# MassHackersBadge2015.net
KiCad netlist of a schematic drawn in EAGLE
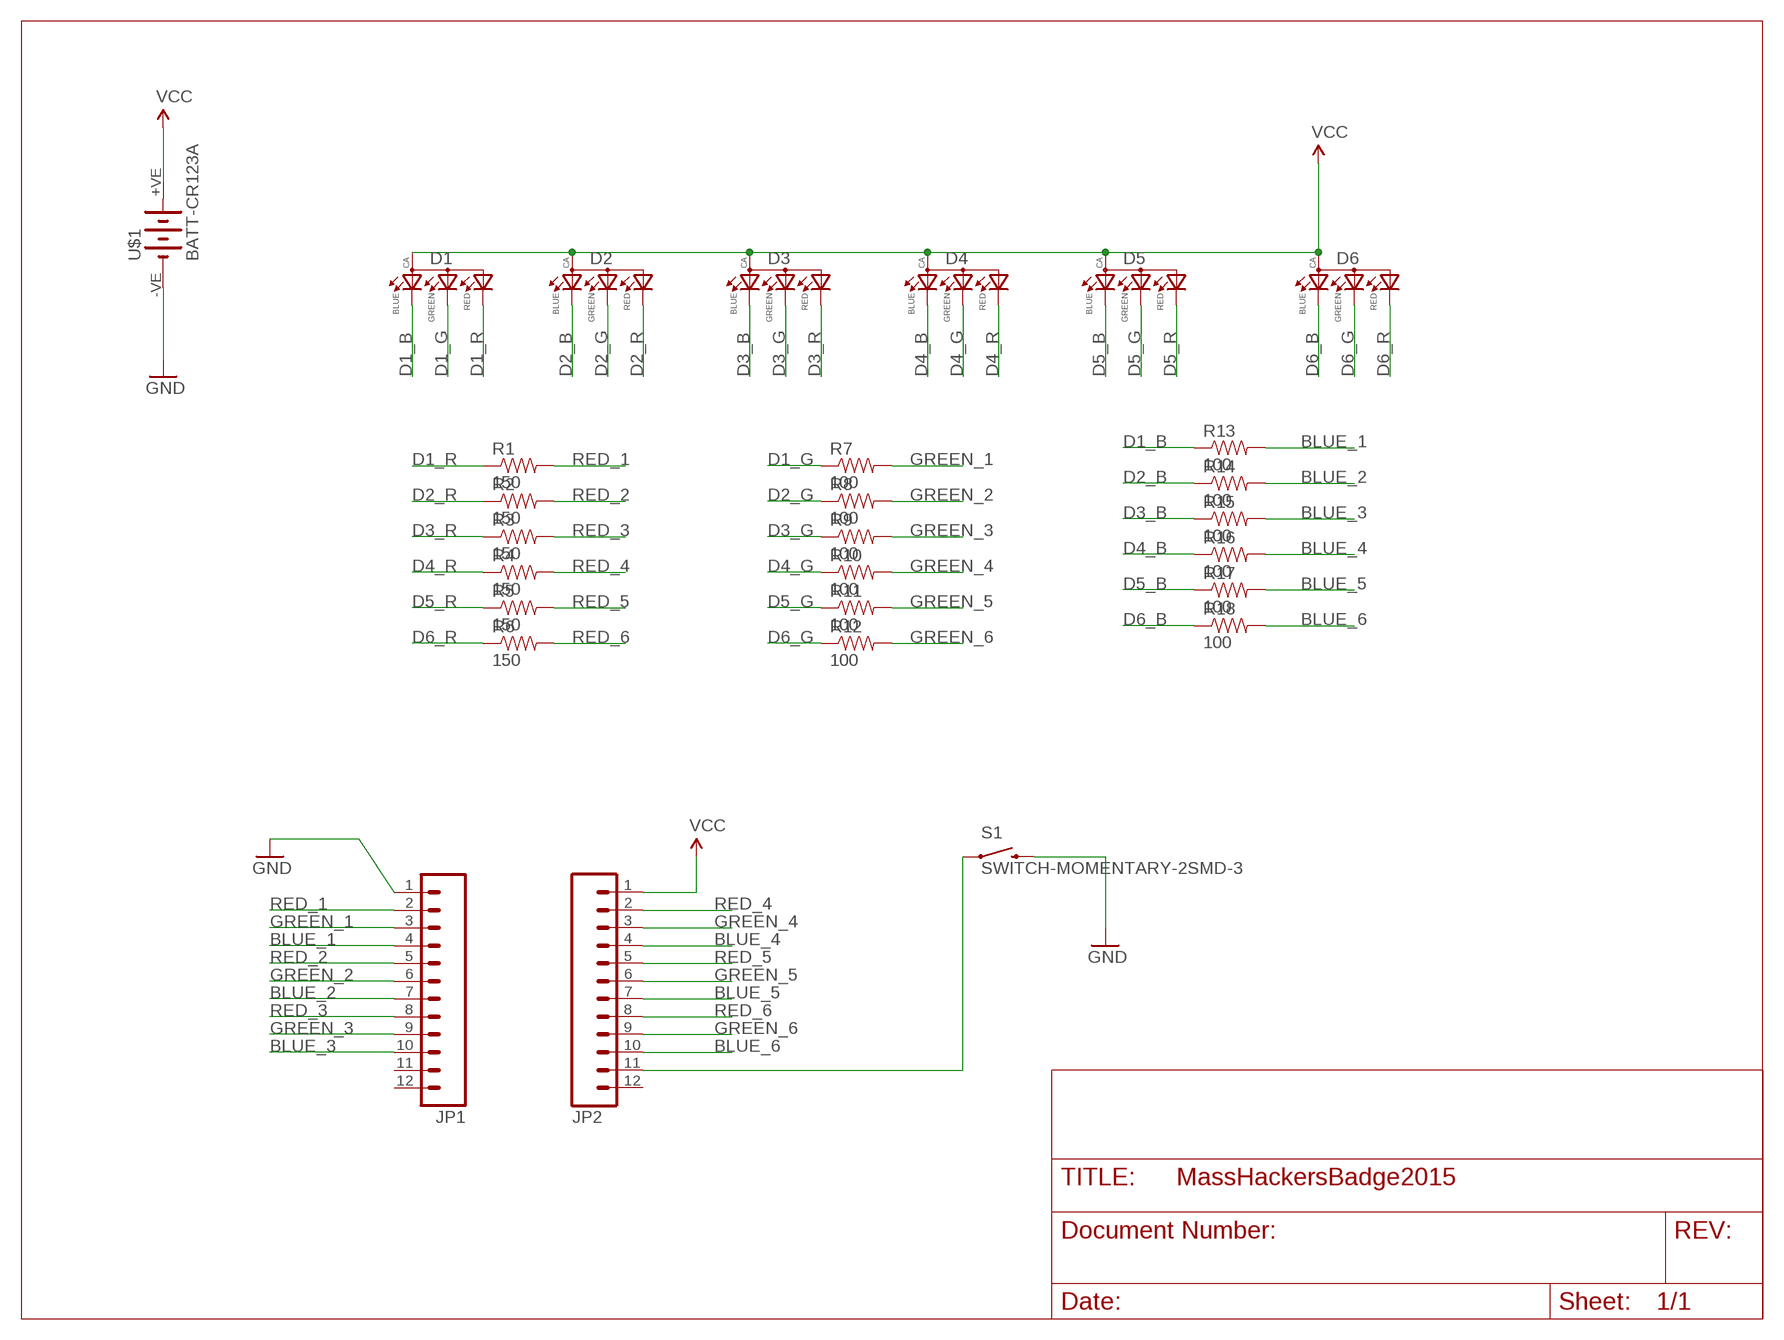
[diagram p0: schematic, sheet 1]

(export (version "E")
  (design (tool "Eeschema 10.0.6"))
  (components
    (comp (ref "D1")
      (value "0.13_RGB_LEDPLCC")
      (footprint "eagle-import:P-LCC-4-3")
      (libsource (lib "eagle-import") (part "0.13_RGB_LEDPLCC"))
    )
    (comp (ref "D2")
      (value "0.13_RGB_LEDPLCC")
      (footprint "eagle-import:P-LCC-4-3")
      (libsource (lib "eagle-import") (part "0.13_RGB_LEDPLCC"))
    )
    (comp (ref "D3")
      (value "0.13_RGB_LEDPLCC")
      (footprint "eagle-import:P-LCC-4-3")
      (libsource (lib "eagle-import") (part "0.13_RGB_LEDPLCC"))
    )
    (comp (ref "D4")
      (value "0.13_RGB_LEDPLCC")
      (footprint "eagle-import:P-LCC-4-3")
      (libsource (lib "eagle-import") (part "0.13_RGB_LEDPLCC"))
    )
    (comp (ref "D5")
      (value "0.13_RGB_LEDPLCC")
      (footprint "eagle-import:P-LCC-4-3")
      (libsource (lib "eagle-import") (part "0.13_RGB_LEDPLCC"))
    )
    (comp (ref "D6")
      (value "0.13_RGB_LEDPLCC")
      (footprint "eagle-import:P-LCC-4-3")
      (libsource (lib "eagle-import") (part "0.13_RGB_LEDPLCC"))
    )
    (comp (ref "JP1")
      (value "M12PTH")
      (footprint "eagle-import:1X12")
      (libsource (lib "eagle-import") (part "M12PTH"))
    )
    (comp (ref "JP2")
      (value "M12PTH")
      (footprint "eagle-import:1X12")
      (libsource (lib "eagle-import") (part "M12PTH"))
    )
    (comp (ref "R1")
      (value "150")
      (footprint "eagle-import:0603-RES")
      (libsource (lib "eagle-import") (part "RESISTOR0603-RES"))
    )
    (comp (ref "R2")
      (value "150")
      (footprint "eagle-import:0603-RES")
      (libsource (lib "eagle-import") (part "RESISTOR0603-RES"))
    )
    (comp (ref "R3")
      (value "150")
      (footprint "eagle-import:0603-RES")
      (libsource (lib "eagle-import") (part "RESISTOR0603-RES"))
    )
    (comp (ref "R4")
      (value "150")
      (footprint "eagle-import:0603-RES")
      (libsource (lib "eagle-import") (part "RESISTOR0603-RES"))
    )
    (comp (ref "R5")
      (value "150")
      (footprint "eagle-import:0603-RES")
      (libsource (lib "eagle-import") (part "RESISTOR0603-RES"))
    )
    (comp (ref "R6")
      (value "150")
      (footprint "eagle-import:0603-RES")
      (libsource (lib "eagle-import") (part "RESISTOR0603-RES"))
    )
    (comp (ref "R7")
      (value "100")
      (footprint "eagle-import:0603-RES")
      (libsource (lib "eagle-import") (part "RESISTOR0603-RES"))
    )
    (comp (ref "R8")
      (value "100")
      (footprint "eagle-import:0603-RES")
      (libsource (lib "eagle-import") (part "RESISTOR0603-RES"))
    )
    (comp (ref "R9")
      (value "100")
      (footprint "eagle-import:0603-RES")
      (libsource (lib "eagle-import") (part "RESISTOR0603-RES"))
    )
    (comp (ref "R10")
      (value "100")
      (footprint "eagle-import:0603-RES")
      (libsource (lib "eagle-import") (part "RESISTOR0603-RES"))
    )
    (comp (ref "R11")
      (value "100")
      (footprint "eagle-import:0603-RES")
      (libsource (lib "eagle-import") (part "RESISTOR0603-RES"))
    )
    (comp (ref "R12")
      (value "100")
      (footprint "eagle-import:0603-RES")
      (libsource (lib "eagle-import") (part "RESISTOR0603-RES"))
    )
    (comp (ref "R13")
      (value "100")
      (footprint "eagle-import:0603-RES")
      (libsource (lib "eagle-import") (part "RESISTOR0603-RES"))
    )
    (comp (ref "R14")
      (value "100")
      (footprint "eagle-import:0603-RES")
      (libsource (lib "eagle-import") (part "RESISTOR0603-RES"))
    )
    (comp (ref "R15")
      (value "100")
      (footprint "eagle-import:0603-RES")
      (libsource (lib "eagle-import") (part "RESISTOR0603-RES"))
    )
    (comp (ref "R16")
      (value "100")
      (footprint "eagle-import:0603-RES")
      (libsource (lib "eagle-import") (part "RESISTOR0603-RES"))
    )
    (comp (ref "R17")
      (value "100")
      (footprint "eagle-import:0603-RES")
      (libsource (lib "eagle-import") (part "RESISTOR0603-RES"))
    )
    (comp (ref "R18")
      (value "100")
      (footprint "eagle-import:0603-RES")
      (libsource (lib "eagle-import") (part "RESISTOR0603-RES"))
    )
    (comp (ref "S1")
      (value "SWITCH-MOMENTARY-2SMD-3")
      (footprint "eagle-import:TACTILE_SWITCH_SMD-3")
      (libsource (lib "eagle-import") (part "SWITCH-MOMENTARY-2SMD-3"))
    )
    (comp (ref "U$1")
      (value "BATT-CR123A")
      (footprint "eagle-import:KEYSTONE-2_3A")
      (libsource (lib "eagle-import") (part "BATT-CR123A"))
    )
  )
  (nets
    (net (code "1") (name "/BLUE_1") (class "Default")
      (node (ref "JP1") (pin "4") (pinfunction "4_4") (pintype "passive"))
      (node (ref "R13") (pin "2") (pinfunction "2_2") (pintype "passive"))
    )
    (net (code "2") (name "/BLUE_2") (class "Default")
      (node (ref "JP1") (pin "7") (pinfunction "7_7") (pintype "passive"))
      (node (ref "R14") (pin "2") (pinfunction "2_2") (pintype "passive"))
    )
    (net (code "3") (name "/BLUE_3") (class "Default")
      (node (ref "JP1") (pin "10") (pinfunction "10_10") (pintype "passive"))
      (node (ref "R15") (pin "2") (pinfunction "2_2") (pintype "passive"))
    )
    (net (code "4") (name "/BLUE_4") (class "Default")
      (node (ref "JP2") (pin "4") (pinfunction "4_4") (pintype "passive"))
      (node (ref "R16") (pin "2") (pinfunction "2_2") (pintype "passive"))
    )
    (net (code "5") (name "/BLUE_5") (class "Default")
      (node (ref "JP2") (pin "7") (pinfunction "7_7") (pintype "passive"))
      (node (ref "R17") (pin "2") (pinfunction "2_2") (pintype "passive"))
    )
    (net (code "6") (name "/BLUE_6") (class "Default")
      (node (ref "JP2") (pin "10") (pinfunction "10_10") (pintype "passive"))
      (node (ref "R18") (pin "2") (pinfunction "2_2") (pintype "passive"))
    )
    (net (code "7") (name "/D1_B") (class "Default")
      (node (ref "D1") (pin "3") (pinfunction "BLUE_3") (pintype "passive"))
      (node (ref "R13") (pin "1") (pinfunction "1_1") (pintype "passive"))
    )
    (net (code "8") (name "/D1_G") (class "Default")
      (node (ref "D1") (pin "2") (pinfunction "GREEN_2") (pintype "passive"))
      (node (ref "R7") (pin "1") (pinfunction "1_1") (pintype "passive"))
    )
    (net (code "9") (name "/D1_R") (class "Default")
      (node (ref "D1") (pin "1") (pinfunction "RED_1") (pintype "passive"))
      (node (ref "R1") (pin "1") (pinfunction "1_1") (pintype "passive"))
    )
    (net (code "10") (name "/D2_B") (class "Default")
      (node (ref "D2") (pin "3") (pinfunction "BLUE_3") (pintype "passive"))
      (node (ref "R14") (pin "1") (pinfunction "1_1") (pintype "passive"))
    )
    (net (code "11") (name "/D2_G") (class "Default")
      (node (ref "D2") (pin "2") (pinfunction "GREEN_2") (pintype "passive"))
      (node (ref "R8") (pin "1") (pinfunction "1_1") (pintype "passive"))
    )
    (net (code "12") (name "/D2_R") (class "Default")
      (node (ref "D2") (pin "1") (pinfunction "RED_1") (pintype "passive"))
      (node (ref "R2") (pin "1") (pinfunction "1_1") (pintype "passive"))
    )
    (net (code "13") (name "/D3_B") (class "Default")
      (node (ref "D3") (pin "3") (pinfunction "BLUE_3") (pintype "passive"))
      (node (ref "R15") (pin "1") (pinfunction "1_1") (pintype "passive"))
    )
    (net (code "14") (name "/D3_G") (class "Default")
      (node (ref "D3") (pin "2") (pinfunction "GREEN_2") (pintype "passive"))
      (node (ref "R9") (pin "1") (pinfunction "1_1") (pintype "passive"))
    )
    (net (code "15") (name "/D3_R") (class "Default")
      (node (ref "D3") (pin "1") (pinfunction "RED_1") (pintype "passive"))
      (node (ref "R3") (pin "1") (pinfunction "1_1") (pintype "passive"))
    )
    (net (code "16") (name "/D4_B") (class "Default")
      (node (ref "D4") (pin "3") (pinfunction "BLUE_3") (pintype "passive"))
      (node (ref "R16") (pin "1") (pinfunction "1_1") (pintype "passive"))
    )
    (net (code "17") (name "/D4_G") (class "Default")
      (node (ref "D4") (pin "2") (pinfunction "GREEN_2") (pintype "passive"))
      (node (ref "R10") (pin "1") (pinfunction "1_1") (pintype "passive"))
    )
    (net (code "18") (name "/D4_R") (class "Default")
      (node (ref "D4") (pin "1") (pinfunction "RED_1") (pintype "passive"))
      (node (ref "R4") (pin "1") (pinfunction "1_1") (pintype "passive"))
    )
    (net (code "19") (name "/D5_B") (class "Default")
      (node (ref "D5") (pin "3") (pinfunction "BLUE_3") (pintype "passive"))
      (node (ref "R17") (pin "1") (pinfunction "1_1") (pintype "passive"))
    )
    (net (code "20") (name "/D5_G") (class "Default")
      (node (ref "D5") (pin "2") (pinfunction "GREEN_2") (pintype "passive"))
      (node (ref "R11") (pin "1") (pinfunction "1_1") (pintype "passive"))
    )
    (net (code "21") (name "/D5_R") (class "Default")
      (node (ref "D5") (pin "1") (pinfunction "RED_1") (pintype "passive"))
      (node (ref "R5") (pin "1") (pinfunction "1_1") (pintype "passive"))
    )
    (net (code "22") (name "/D6_B") (class "Default")
      (node (ref "D6") (pin "3") (pinfunction "BLUE_3") (pintype "passive"))
      (node (ref "R18") (pin "1") (pinfunction "1_1") (pintype "passive"))
    )
    (net (code "23") (name "/D6_G") (class "Default")
      (node (ref "D6") (pin "2") (pinfunction "GREEN_2") (pintype "passive"))
      (node (ref "R12") (pin "1") (pinfunction "1_1") (pintype "passive"))
    )
    (net (code "24") (name "/D6_R") (class "Default")
      (node (ref "D6") (pin "1") (pinfunction "RED_1") (pintype "passive"))
      (node (ref "R6") (pin "1") (pinfunction "1_1") (pintype "passive"))
    )
    (net (code "25") (name "/GREEN_1") (class "Default")
      (node (ref "JP1") (pin "3") (pinfunction "3_3") (pintype "passive"))
      (node (ref "R7") (pin "2") (pinfunction "2_2") (pintype "passive"))
    )
    (net (code "26") (name "/GREEN_2") (class "Default")
      (node (ref "JP1") (pin "6") (pinfunction "6_6") (pintype "passive"))
      (node (ref "R8") (pin "2") (pinfunction "2_2") (pintype "passive"))
    )
    (net (code "27") (name "/GREEN_3") (class "Default")
      (node (ref "JP1") (pin "9") (pinfunction "9_9") (pintype "passive"))
      (node (ref "R9") (pin "2") (pinfunction "2_2") (pintype "passive"))
    )
    (net (code "28") (name "/GREEN_4") (class "Default")
      (node (ref "JP2") (pin "3") (pinfunction "3_3") (pintype "passive"))
      (node (ref "R10") (pin "2") (pinfunction "2_2") (pintype "passive"))
    )
    (net (code "29") (name "/GREEN_5") (class "Default")
      (node (ref "JP2") (pin "6") (pinfunction "6_6") (pintype "passive"))
      (node (ref "R11") (pin "2") (pinfunction "2_2") (pintype "passive"))
    )
    (net (code "30") (name "/GREEN_6") (class "Default")
      (node (ref "JP2") (pin "9") (pinfunction "9_9") (pintype "passive"))
      (node (ref "R12") (pin "2") (pinfunction "2_2") (pintype "passive"))
    )
    (net (code "31") (name "/RED_1") (class "Default")
      (node (ref "JP1") (pin "2") (pinfunction "2_2") (pintype "passive"))
      (node (ref "R1") (pin "2") (pinfunction "2_2") (pintype "passive"))
    )
    (net (code "32") (name "/RED_2") (class "Default")
      (node (ref "JP1") (pin "5") (pinfunction "5_5") (pintype "passive"))
      (node (ref "R2") (pin "2") (pinfunction "2_2") (pintype "passive"))
    )
    (net (code "33") (name "/RED_3") (class "Default")
      (node (ref "JP1") (pin "8") (pinfunction "8_8") (pintype "passive"))
      (node (ref "R3") (pin "2") (pinfunction "2_2") (pintype "passive"))
    )
    (net (code "34") (name "/RED_4") (class "Default")
      (node (ref "JP2") (pin "2") (pinfunction "2_2") (pintype "passive"))
      (node (ref "R4") (pin "2") (pinfunction "2_2") (pintype "passive"))
    )
    (net (code "35") (name "/RED_5") (class "Default")
      (node (ref "JP2") (pin "5") (pinfunction "5_5") (pintype "passive"))
      (node (ref "R5") (pin "2") (pinfunction "2_2") (pintype "passive"))
    )
    (net (code "36") (name "/RED_6") (class "Default")
      (node (ref "JP2") (pin "8") (pinfunction "8_8") (pintype "passive"))
      (node (ref "R6") (pin "2") (pinfunction "2_2") (pintype "passive"))
    )
    (net (code "37") (name "GND") (class "Default")
      (node (ref "JP1") (pin "1") (pinfunction "1_1") (pintype "passive"))
      (node (ref "S1") (pin "4") (pinfunction "2_4") (pintype "passive"))
      (node (ref "U$1") (pin "-VE") (pinfunction "-_-VE") (pintype "passive"))
    )
    (net (code "38") (name "Net-(JP2-Pad11)") (class "Default")
      (node (ref "JP2") (pin "11") (pinfunction "11_11") (pintype "passive"))
      (node (ref "S1") (pin "1") (pinfunction "1_1") (pintype "passive"))
    )
    (net (code "39") (name "VCC") (class "Default")
      (node (ref "D1") (pin "4") (pinfunction "ANODE_4") (pintype "passive"))
      (node (ref "D2") (pin "4") (pinfunction "ANODE_4") (pintype "passive"))
      (node (ref "D3") (pin "4") (pinfunction "ANODE_4") (pintype "passive"))
      (node (ref "D4") (pin "4") (pinfunction "ANODE_4") (pintype "passive"))
      (node (ref "D5") (pin "4") (pinfunction "ANODE_4") (pintype "passive"))
      (node (ref "D6") (pin "4") (pinfunction "ANODE_4") (pintype "passive"))
      (node (ref "JP2") (pin "1") (pinfunction "1_1") (pintype "passive"))
      (node (ref "U$1") (pin "+VE") (pinfunction "+_+VE") (pintype "passive"))
    )
    (net (code "40") (name "unconnected-(JP1-Pad11)") (class "Default")
      (node (ref "JP1") (pin "11") (pinfunction "11_11") (pintype "passive"))
    )
    (net (code "41") (name "unconnected-(JP1-Pad12)") (class "Default")
      (node (ref "JP1") (pin "12") (pinfunction "12_12") (pintype "passive"))
    )
    (net (code "42") (name "unconnected-(JP2-Pad12)") (class "Default")
      (node (ref "JP2") (pin "12") (pinfunction "12_12") (pintype "passive"))
    )
  )
)
